# EXM_Relay_Three_-_Rev_A2.net
KiCad netlist of a schematic drawn in EAGLE
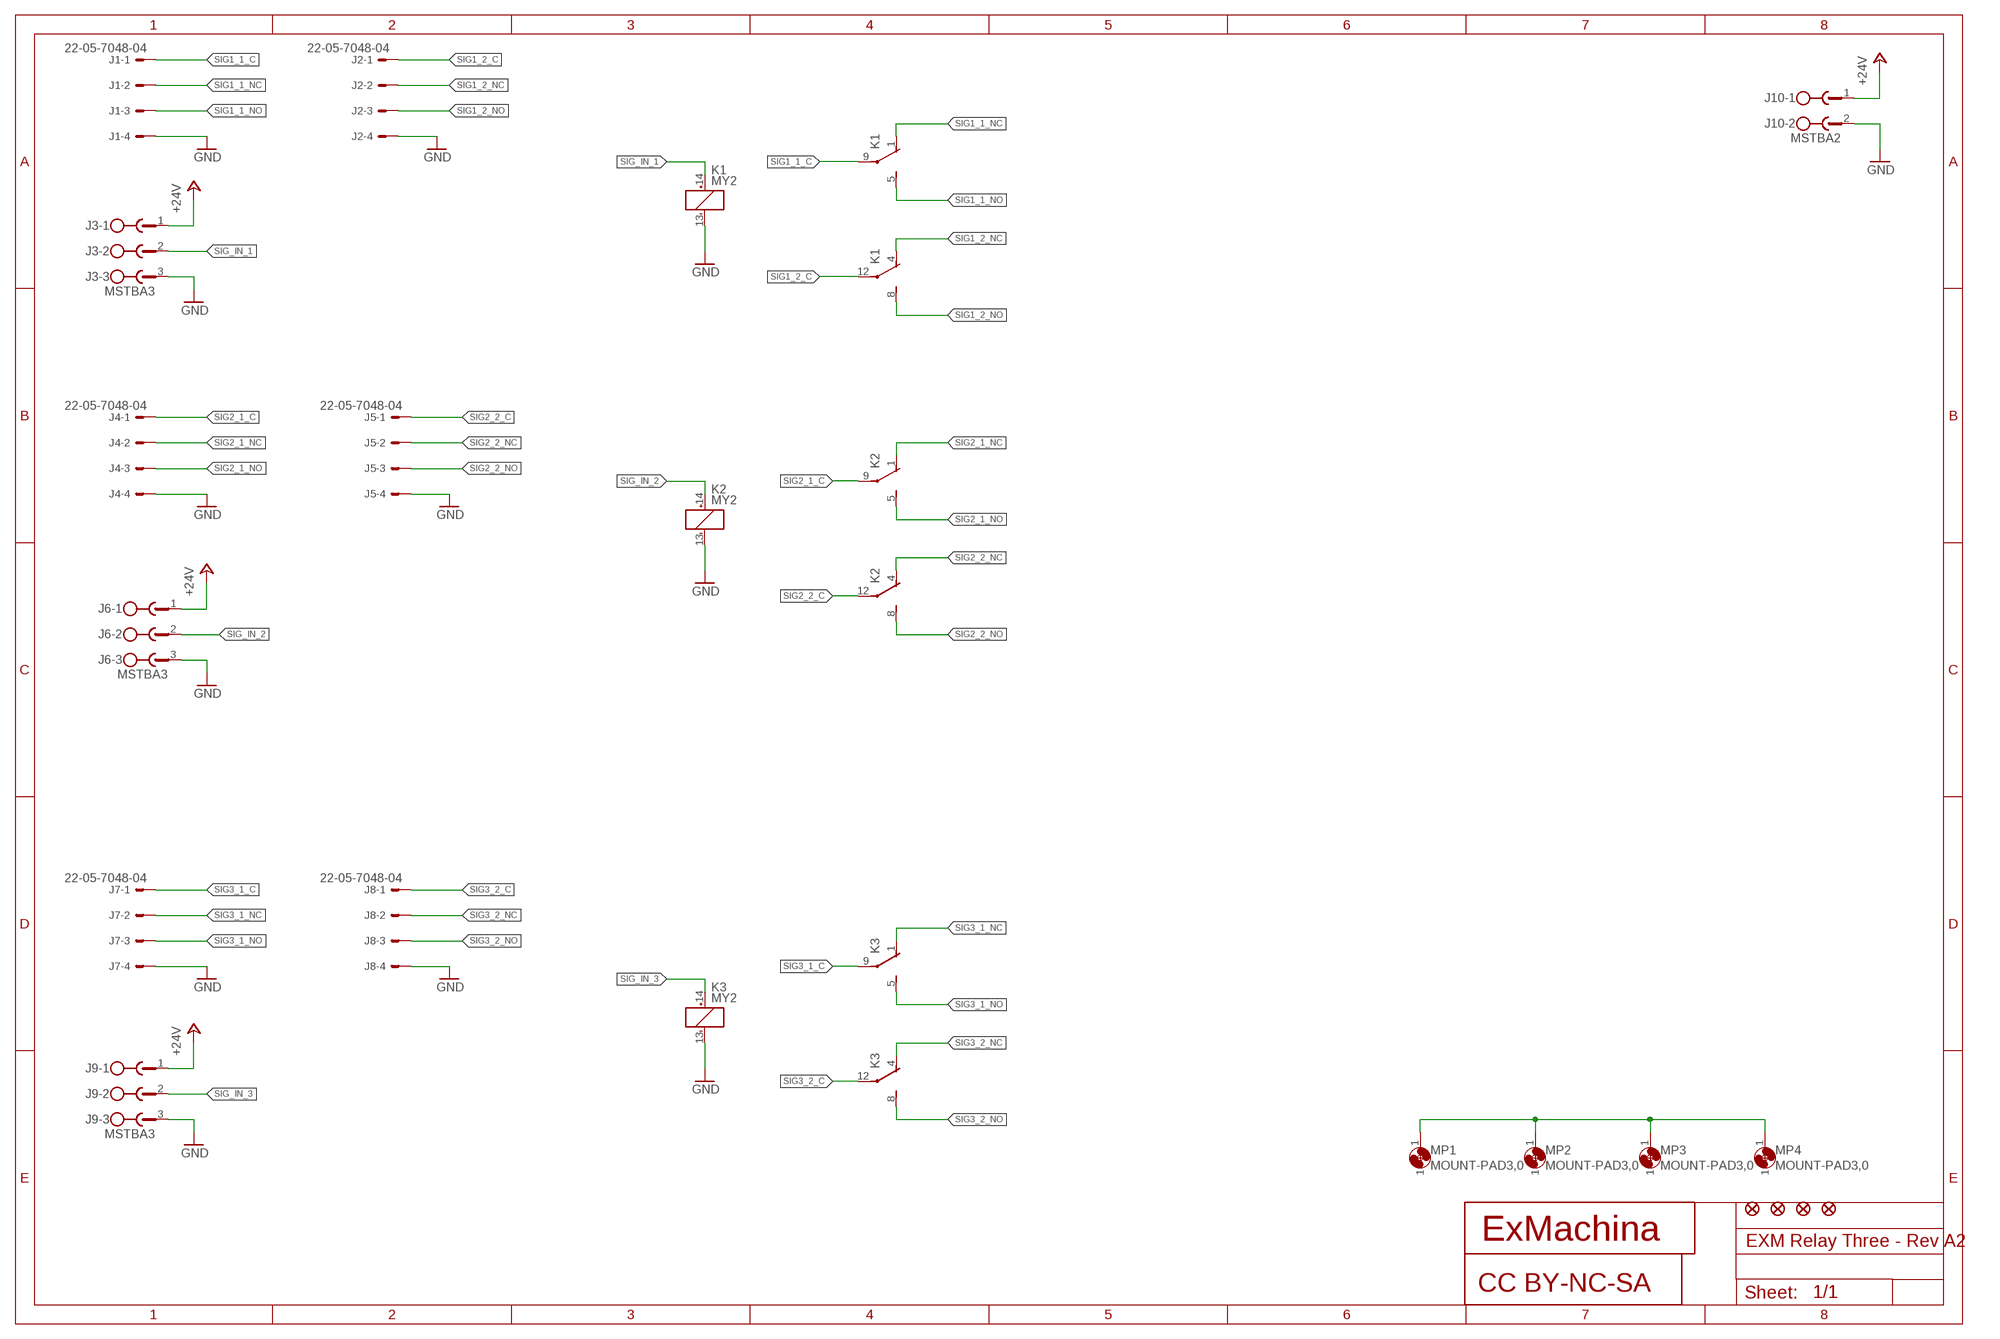
[diagram p0: schematic, sheet 1]

(export (version "E")
  (design (tool "Eeschema 10.0.6"))
  (components
    (comp (ref "CC1")
      (value "CC-BY-NC-SA")
      (footprint "eagle-import:CC-BY-NC-SA")
      (libsource (lib "eagle-import") (part "CC-BY-NC-SA"))
    )
    (comp (ref "J1")
      (value "22-05-7048-04")
      (footprint "eagle-import:7395-04")
      (libsource (lib "eagle-import") (part "22-?-0405-7048"))
    )
    (comp (ref "J2")
      (value "22-05-7048-04")
      (footprint "eagle-import:7395-04")
      (libsource (lib "eagle-import") (part "22-?-0405-7048"))
    )
    (comp (ref "J3")
      (value "MSTBA3")
      (footprint "eagle-import:MSTBA3")
      (fields (field (name "MF") "FARNELL") (field (name "MPN") "1757255"))
      (libsource (lib "eagle-import") (part "MSTBA3"))
    )
    (comp (ref "J4")
      (value "22-05-7048-04")
      (footprint "eagle-import:7395-04")
      (libsource (lib "eagle-import") (part "22-?-0405-7048"))
    )
    (comp (ref "J5")
      (value "22-05-7048-04")
      (footprint "eagle-import:7395-04")
      (libsource (lib "eagle-import") (part "22-?-0405-7048"))
    )
    (comp (ref "J6")
      (value "MSTBA3")
      (footprint "eagle-import:MSTBA3")
      (fields (field (name "MF") "FARNELL") (field (name "MPN") "1757255"))
      (libsource (lib "eagle-import") (part "MSTBA3"))
    )
    (comp (ref "J7")
      (value "22-05-7048-04")
      (footprint "eagle-import:7395-04")
      (libsource (lib "eagle-import") (part "22-?-0405-7048"))
    )
    (comp (ref "J8")
      (value "22-05-7048-04")
      (footprint "eagle-import:7395-04")
      (libsource (lib "eagle-import") (part "22-?-0405-7048"))
    )
    (comp (ref "J9")
      (value "MSTBA3")
      (footprint "eagle-import:MSTBA3")
      (fields (field (name "MF") "FARNELL") (field (name "MPN") "1757255"))
      (libsource (lib "eagle-import") (part "MSTBA3"))
    )
    (comp (ref "J10")
      (value "MSTBA2")
      (footprint "eagle-import:MSTBA2")
      (fields (field (name "MF") "FARNELL") (field (name "MPN") "1757242"))
      (libsource (lib "eagle-import") (part "MSTBA2"))
    )
    (comp (ref "JP1")
      (value "FIDUCIAL1X2")
      (footprint "eagle-import:FIDUCIAL-1X2")
      (libsource (lib "eagle-import") (part "FIDUCIAL1X2"))
    )
    (comp (ref "JP2")
      (value "FIDUCIAL1X2")
      (footprint "eagle-import:FIDUCIAL-1X2")
      (libsource (lib "eagle-import") (part "FIDUCIAL1X2"))
    )
    (comp (ref "JP3")
      (value "FIDUCIAL1X2")
      (footprint "eagle-import:FIDUCIAL-1X2")
      (libsource (lib "eagle-import") (part "FIDUCIAL1X2"))
    )
    (comp (ref "JP4")
      (value "FIDUCIAL1X2")
      (footprint "eagle-import:FIDUCIAL-1X2")
      (libsource (lib "eagle-import") (part "FIDUCIAL1X2"))
    )
    (comp (ref "K1")
      (value "MY2")
      (footprint "eagle-import:PY08")
      (fields
        (field (name "MF") "OMRON COMPONENTS USA")
        (field (name "MPN") "PY08")
        (field (name "OC_NEWARK") "36K3464")
      )
      (libsource (lib "eagle-import") (part "MY2"))
    )
    (comp (ref "K2")
      (value "MY2")
      (footprint "eagle-import:PY08")
      (fields
        (field (name "MF") "OMRON COMPONENTS USA")
        (field (name "MPN") "PY08")
        (field (name "OC_NEWARK") "36K3464")
      )
      (libsource (lib "eagle-import") (part "MY2"))
    )
    (comp (ref "K3")
      (value "MY2")
      (footprint "eagle-import:PY08")
      (fields
        (field (name "MF") "OMRON COMPONENTS USA")
        (field (name "MPN") "PY08")
        (field (name "OC_NEWARK") "36K3464")
      )
      (libsource (lib "eagle-import") (part "MY2"))
    )
    (comp (ref "MP1")
      (value "MOUNT-PAD3,0")
      (footprint "eagle-import:P3,0")
      (libsource (lib "eagle-import") (part "MOUNT-PAD3,0"))
    )
    (comp (ref "MP2")
      (value "MOUNT-PAD3,0")
      (footprint "eagle-import:P3,0")
      (libsource (lib "eagle-import") (part "MOUNT-PAD3,0"))
    )
    (comp (ref "MP3")
      (value "MOUNT-PAD3,0")
      (footprint "eagle-import:P3,0")
      (libsource (lib "eagle-import") (part "MOUNT-PAD3,0"))
    )
    (comp (ref "MP4")
      (value "MOUNT-PAD3,0")
      (footprint "eagle-import:P3,0")
      (libsource (lib "eagle-import") (part "MOUNT-PAD3,0"))
    )
    (comp (ref "T1")
      (value "EXMACHINA-LOGO-NAME")
      (footprint "eagle-import:EXM-LOGO-BASELINE")
      (libsource (lib "eagle-import") (part "EXMACHINA-LOGO-NAME"))
    )
  )
  (nets
    (net (code "1") (name "+24V") (class "Default")
      (node (ref "J10") (pin "1") (pinfunction "1_1") (pintype "passive"))
      (node (ref "J3") (pin "1") (pinfunction "1_1") (pintype "passive"))
      (node (ref "J6") (pin "1") (pinfunction "1_1") (pintype "passive"))
      (node (ref "J9") (pin "1") (pinfunction "1_1") (pintype "passive"))
    )
    (net (code "2") (name "GND") (class "Default")
      (node (ref "J1") (pin "4") (pinfunction "S_4") (pintype "passive"))
      (node (ref "J10") (pin "2") (pinfunction "1_2") (pintype "passive"))
      (node (ref "J2") (pin "4") (pinfunction "S_4") (pintype "passive"))
      (node (ref "J3") (pin "3") (pinfunction "1_3") (pintype "passive"))
      (node (ref "J4") (pin "4") (pinfunction "S_4") (pintype "passive"))
      (node (ref "J5") (pin "4") (pinfunction "S_4") (pintype "passive"))
      (node (ref "J6") (pin "3") (pinfunction "1_3") (pintype "passive"))
      (node (ref "J7") (pin "4") (pinfunction "S_4") (pintype "passive"))
      (node (ref "J8") (pin "4") (pinfunction "S_4") (pintype "passive"))
      (node (ref "J9") (pin "3") (pinfunction "1_3") (pintype "passive"))
      (node (ref "K1") (pin "13") (pinfunction "-_13") (pintype "passive"))
      (node (ref "K2") (pin "13") (pinfunction "-_13") (pintype "passive"))
      (node (ref "K3") (pin "13") (pinfunction "-_13") (pintype "passive"))
    )
    (net (code "3") (name "MOUNT-PAD3,0") (class "Default")
      (node (ref "MP1") (pin "1") (pinfunction "1_1") (pintype "power_in"))
      (node (ref "MP2") (pin "1") (pinfunction "1_1") (pintype "power_in"))
      (node (ref "MP3") (pin "1") (pinfunction "1_1") (pintype "power_in"))
      (node (ref "MP4") (pin "1") (pinfunction "1_1") (pintype "power_in"))
    )
    (net (code "4") (name "SIG1_1_C") (class "Default")
      (node (ref "J1") (pin "1") (pinfunction "S_1") (pintype "passive"))
      (node (ref "K1") (pin "9") (pinfunction "C_9") (pintype "passive"))
    )
    (net (code "5") (name "SIG1_1_NC") (class "Default")
      (node (ref "J1") (pin "2") (pinfunction "S_2") (pintype "passive"))
      (node (ref "K1") (pin "1") (pinfunction "NC_1") (pintype "passive"))
    )
    (net (code "6") (name "SIG1_1_NO") (class "Default")
      (node (ref "J1") (pin "3") (pinfunction "S_3") (pintype "passive"))
      (node (ref "K1") (pin "5") (pinfunction "NO_5") (pintype "passive"))
    )
    (net (code "7") (name "SIG1_2_C") (class "Default")
      (node (ref "J2") (pin "1") (pinfunction "S_1") (pintype "passive"))
      (node (ref "K1") (pin "12") (pinfunction "C_12") (pintype "passive"))
    )
    (net (code "8") (name "SIG1_2_NC") (class "Default")
      (node (ref "J2") (pin "2") (pinfunction "S_2") (pintype "passive"))
      (node (ref "K1") (pin "4") (pinfunction "NC_4") (pintype "passive"))
    )
    (net (code "9") (name "SIG1_2_NO") (class "Default")
      (node (ref "J2") (pin "3") (pinfunction "S_3") (pintype "passive"))
      (node (ref "K1") (pin "8") (pinfunction "NO_8") (pintype "passive"))
    )
    (net (code "10") (name "SIG2_1_C") (class "Default")
      (node (ref "J4") (pin "1") (pinfunction "S_1") (pintype "passive"))
      (node (ref "K2") (pin "9") (pinfunction "C_9") (pintype "passive"))
    )
    (net (code "11") (name "SIG2_1_NC") (class "Default")
      (node (ref "J4") (pin "2") (pinfunction "S_2") (pintype "passive"))
      (node (ref "K2") (pin "1") (pinfunction "NC_1") (pintype "passive"))
    )
    (net (code "12") (name "SIG2_1_NO") (class "Default")
      (node (ref "J4") (pin "3") (pinfunction "S_3") (pintype "passive"))
      (node (ref "K2") (pin "5") (pinfunction "NO_5") (pintype "passive"))
    )
    (net (code "13") (name "SIG2_2_C") (class "Default")
      (node (ref "J5") (pin "1") (pinfunction "S_1") (pintype "passive"))
      (node (ref "K2") (pin "12") (pinfunction "C_12") (pintype "passive"))
    )
    (net (code "14") (name "SIG2_2_NC") (class "Default")
      (node (ref "J5") (pin "2") (pinfunction "S_2") (pintype "passive"))
      (node (ref "K2") (pin "4") (pinfunction "NC_4") (pintype "passive"))
    )
    (net (code "15") (name "SIG2_2_NO") (class "Default")
      (node (ref "J5") (pin "3") (pinfunction "S_3") (pintype "passive"))
      (node (ref "K2") (pin "8") (pinfunction "NO_8") (pintype "passive"))
    )
    (net (code "16") (name "SIG3_1_C") (class "Default")
      (node (ref "J7") (pin "1") (pinfunction "S_1") (pintype "passive"))
      (node (ref "K3") (pin "9") (pinfunction "C_9") (pintype "passive"))
    )
    (net (code "17") (name "SIG3_1_NC") (class "Default")
      (node (ref "J7") (pin "2") (pinfunction "S_2") (pintype "passive"))
      (node (ref "K3") (pin "1") (pinfunction "NC_1") (pintype "passive"))
    )
    (net (code "18") (name "SIG3_1_NO") (class "Default")
      (node (ref "J7") (pin "3") (pinfunction "S_3") (pintype "passive"))
      (node (ref "K3") (pin "5") (pinfunction "NO_5") (pintype "passive"))
    )
    (net (code "19") (name "SIG3_2_C") (class "Default")
      (node (ref "J8") (pin "1") (pinfunction "S_1") (pintype "passive"))
      (node (ref "K3") (pin "12") (pinfunction "C_12") (pintype "passive"))
    )
    (net (code "20") (name "SIG3_2_NC") (class "Default")
      (node (ref "J8") (pin "2") (pinfunction "S_2") (pintype "passive"))
      (node (ref "K3") (pin "4") (pinfunction "NC_4") (pintype "passive"))
    )
    (net (code "21") (name "SIG3_2_NO") (class "Default")
      (node (ref "J8") (pin "3") (pinfunction "S_3") (pintype "passive"))
      (node (ref "K3") (pin "8") (pinfunction "NO_8") (pintype "passive"))
    )
    (net (code "22") (name "SIG_IN_1") (class "Default")
      (node (ref "J3") (pin "2") (pinfunction "1_2") (pintype "passive"))
      (node (ref "K1") (pin "14") (pinfunction "+_14") (pintype "passive"))
    )
    (net (code "23") (name "SIG_IN_2") (class "Default")
      (node (ref "J6") (pin "2") (pinfunction "1_2") (pintype "passive"))
      (node (ref "K2") (pin "14") (pinfunction "+_14") (pintype "passive"))
    )
    (net (code "24") (name "SIG_IN_3") (class "Default")
      (node (ref "J9") (pin "2") (pinfunction "1_2") (pintype "passive"))
      (node (ref "K3") (pin "14") (pinfunction "+_14") (pintype "passive"))
    )
  )
)
